# Monlock5x7_B.net
KiCad netlist of a schematic drawn in EAGLE
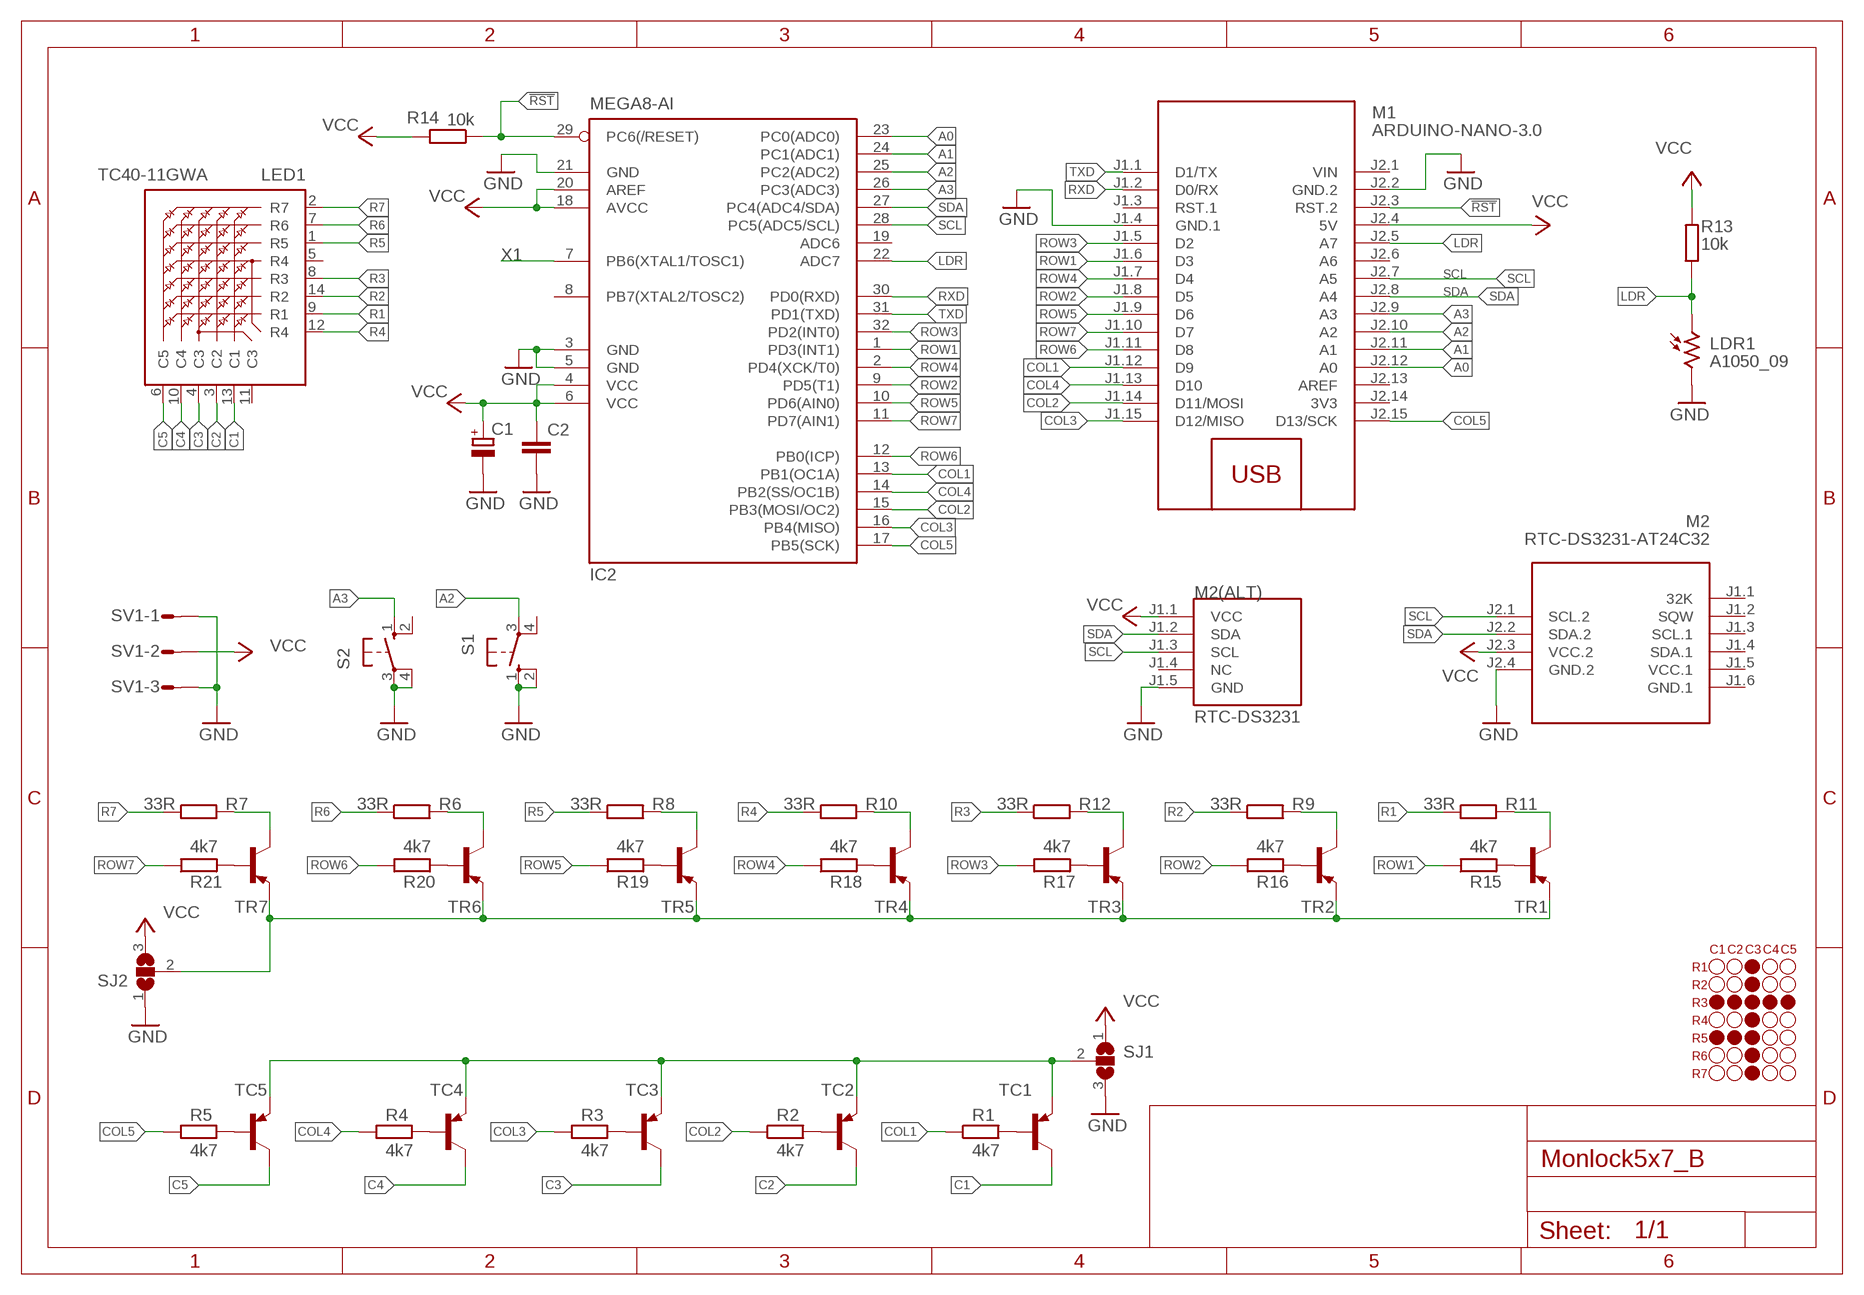
[diagram p0: schematic, sheet 1]

(export (version "E")
  (design (tool "Eeschema 10.0.6"))
  (components
    (comp (ref "C1")
      (value "CPOL-EU153CLV-0605")
      (footprint "eagle-import:153CLV-0605")
      (libsource (lib "eagle-import") (part "CPOL-EU153CLV-0605"))
    )
    (comp (ref "C2")
      (value "C-EUC0805K")
      (footprint "eagle-import:C0805K")
      (libsource (lib "eagle-import") (part "C-EUC0805K"))
    )
    (comp (ref "IC2")
      (value "MEGA8-AI")
      (footprint "eagle-import:TQFP32-08")
      (fields (field (name "MPN") "ATMEGA8-16AU"))
      (libsource (lib "eagle-import") (part "MEGA8-AI"))
    )
    (comp (ref "LDR1")
      (value "A1050_09")
      (footprint "eagle-import:T0-46-A10XX")
      (libsource (lib "eagle-import") (part "A1050_09"))
    )
    (comp (ref "LED1")
      (value "TC40-11GWA")
      (footprint "eagle-import:TC40-11GWA")
      (libsource (lib "eagle-import") (part "TC40-11GWA"))
    )
    (comp (ref "M1")
      (value "ARDUINO-NANO-3.0")
      (footprint "eagle-import:ARDUINO-NANO-3.0")
      (libsource (lib "eagle-import") (part "ARDUINO-NANO-3.0"))
    )
    (comp (ref "M2")
      (value "RTC-DS3231-AT24C32")
      (footprint "eagle-import:RTC-DS3231-AT24C32")
      (libsource (lib "eagle-import") (part "RTC-DS3231-AT24C32"))
    )
    (comp (ref "M2(ALT)")
      (value "RTC-DS3231")
      (footprint "eagle-import:RTC-DS3231_SMALL")
      (libsource (lib "eagle-import") (part "RTC-DS3231"))
    )
    (comp (ref "R1")
      (value "4k7")
      (footprint "eagle-import:0204_7")
      (libsource (lib "eagle-import") (part "R-EU_0204/7"))
    )
    (comp (ref "R2")
      (value "4k7")
      (footprint "eagle-import:0204_7")
      (libsource (lib "eagle-import") (part "R-EU_0204/7"))
    )
    (comp (ref "R3")
      (value "4k7")
      (footprint "eagle-import:0204_7")
      (libsource (lib "eagle-import") (part "R-EU_0204/7"))
    )
    (comp (ref "R4")
      (value "4k7")
      (footprint "eagle-import:0204_7")
      (libsource (lib "eagle-import") (part "R-EU_0204/7"))
    )
    (comp (ref "R5")
      (value "4k7")
      (footprint "eagle-import:0204_7")
      (libsource (lib "eagle-import") (part "R-EU_0204/7"))
    )
    (comp (ref "R6")
      (value "33R")
      (footprint "eagle-import:0204_7")
      (libsource (lib "eagle-import") (part "R-EU_0204/7"))
    )
    (comp (ref "R7")
      (value "33R")
      (footprint "eagle-import:0204_7")
      (libsource (lib "eagle-import") (part "R-EU_0204/7"))
    )
    (comp (ref "R8")
      (value "33R")
      (footprint "eagle-import:0204_7")
      (libsource (lib "eagle-import") (part "R-EU_0204/7"))
    )
    (comp (ref "R9")
      (value "33R")
      (footprint "eagle-import:0204_7")
      (libsource (lib "eagle-import") (part "R-EU_0204/7"))
    )
    (comp (ref "R10")
      (value "33R")
      (footprint "eagle-import:0204_7")
      (libsource (lib "eagle-import") (part "R-EU_0204/7"))
    )
    (comp (ref "R11")
      (value "33R")
      (footprint "eagle-import:0204_7")
      (libsource (lib "eagle-import") (part "R-EU_0204/7"))
    )
    (comp (ref "R12")
      (value "33R")
      (footprint "eagle-import:0204_7")
      (libsource (lib "eagle-import") (part "R-EU_0204/7"))
    )
    (comp (ref "R13")
      (value "10k")
      (footprint "eagle-import:0204_7")
      (libsource (lib "eagle-import") (part "R-EU_0204/7"))
    )
    (comp (ref "R14")
      (value "10k")
      (footprint "eagle-import:M0805")
      (libsource (lib "eagle-import") (part "R-EU_M0805"))
    )
    (comp (ref "R15")
      (value "4k7")
      (footprint "eagle-import:0204_7")
      (libsource (lib "eagle-import") (part "R-EU_0204/7"))
    )
    (comp (ref "R16")
      (value "4k7")
      (footprint "eagle-import:0204_7")
      (libsource (lib "eagle-import") (part "R-EU_0204/7"))
    )
    (comp (ref "R17")
      (value "4k7")
      (footprint "eagle-import:0204_7")
      (libsource (lib "eagle-import") (part "R-EU_0204/7"))
    )
    (comp (ref "R18")
      (value "4k7")
      (footprint "eagle-import:0204_7")
      (libsource (lib "eagle-import") (part "R-EU_0204/7"))
    )
    (comp (ref "R19")
      (value "4k7")
      (footprint "eagle-import:0204_7")
      (libsource (lib "eagle-import") (part "R-EU_0204/7"))
    )
    (comp (ref "R20")
      (value "4k7")
      (footprint "eagle-import:0204_7")
      (libsource (lib "eagle-import") (part "R-EU_0204/7"))
    )
    (comp (ref "R21")
      (value "4k7")
      (footprint "eagle-import:0204_7")
      (libsource (lib "eagle-import") (part "R-EU_0204/7"))
    )
    (comp (ref "S1")
      (value "40-XX")
      (footprint "eagle-import:B3F-40XX")
      (fields (field (name "MF") "OMRON COMPONENTS USA") (field (name "MPN") "B3F-4000"))
      (libsource (lib "eagle-import") (part "40-XX"))
    )
    (comp (ref "S2")
      (value "40-XX")
      (footprint "eagle-import:B3F-40XX")
      (fields (field (name "MF") "OMRON COMPONENTS USA") (field (name "MPN") "B3F-4000"))
      (libsource (lib "eagle-import") (part "40-XX"))
    )
    (comp (ref "SJ1")
      (value "SJ2W")
      (footprint "eagle-import:SJ_2")
      (libsource (lib "eagle-import") (part "SJ2W"))
    )
    (comp (ref "SJ2")
      (value "SJ2W")
      (footprint "eagle-import:SJ_2")
      (libsource (lib "eagle-import") (part "SJ2W"))
    )
    (comp (ref "SV1")
      (value "S03P")
      (footprint "eagle-import:S03P")
      (libsource (lib "eagle-import") (part "S03P"))
    )
    (comp (ref "TC1")
      (value "BC327-PNP-TO92-EBC")
      (footprint "eagle-import:TO92-EBC")
      (libsource (lib "eagle-import") (part "-PNP-TO92-EBCBC327"))
    )
    (comp (ref "TC2")
      (value "BC327-PNP-TO92-EBC")
      (footprint "eagle-import:TO92-EBC")
      (libsource (lib "eagle-import") (part "-PNP-TO92-EBCBC327"))
    )
    (comp (ref "TC3")
      (value "BC327-PNP-TO92-EBC")
      (footprint "eagle-import:TO92-EBC")
      (libsource (lib "eagle-import") (part "-PNP-TO92-EBCBC327"))
    )
    (comp (ref "TC4")
      (value "BC327-PNP-TO92-EBC")
      (footprint "eagle-import:TO92-EBC")
      (libsource (lib "eagle-import") (part "-PNP-TO92-EBCBC327"))
    )
    (comp (ref "TC5")
      (value "BC327-PNP-TO92-EBC")
      (footprint "eagle-import:TO92-EBC")
      (libsource (lib "eagle-import") (part "-PNP-TO92-EBCBC327"))
    )
    (comp (ref "TR1")
      (value "BC327-PNP-TO92-EBC")
      (footprint "eagle-import:TO92-EBC")
      (libsource (lib "eagle-import") (part "-PNP-TO92-EBCBC327"))
    )
    (comp (ref "TR2")
      (value "BC327-PNP-TO92-EBC")
      (footprint "eagle-import:TO92-EBC")
      (libsource (lib "eagle-import") (part "-PNP-TO92-EBCBC327"))
    )
    (comp (ref "TR3")
      (value "BC327-PNP-TO92-EBC")
      (footprint "eagle-import:TO92-EBC")
      (libsource (lib "eagle-import") (part "-PNP-TO92-EBCBC327"))
    )
    (comp (ref "TR4")
      (value "BC327-PNP-TO92-EBC")
      (footprint "eagle-import:TO92-EBC")
      (libsource (lib "eagle-import") (part "-PNP-TO92-EBCBC327"))
    )
    (comp (ref "TR5")
      (value "BC327-PNP-TO92-EBC")
      (footprint "eagle-import:TO92-EBC")
      (libsource (lib "eagle-import") (part "-PNP-TO92-EBCBC327"))
    )
    (comp (ref "TR6")
      (value "BC327-PNP-TO92-EBC")
      (footprint "eagle-import:TO92-EBC")
      (libsource (lib "eagle-import") (part "-PNP-TO92-EBCBC327"))
    )
    (comp (ref "TR7")
      (value "BC327-PNP-TO92-EBC")
      (footprint "eagle-import:TO92-EBC")
      (libsource (lib "eagle-import") (part "-PNP-TO92-EBCBC327"))
    )
  )
  (nets
    (net (code "1") (name "/3V3") (class "Default")
      (node (ref "M1") (pin "J2.14") (pinfunction "3V3_J2.14") (pintype "power_in"))
    )
    (net (code "2") (name "/GND.1") (class "Default")
      (node (ref "M2") (pin "J1.6") (pinfunction "GND.1_J1.6") (pintype "power_in"))
    )
    (net (code "3") (name "/VCC.1") (class "Default")
      (node (ref "M2") (pin "J1.5") (pinfunction "VCC.1_J1.5") (pintype "power_in"))
    )
    (net (code "4") (name "/VIN") (class "Default")
      (node (ref "M1") (pin "J2.1") (pinfunction "VIN_J2.1") (pintype "power_in"))
    )
    (net (code "5") (name "/X1") (class "Default")
      (node (ref "IC2") (pin "7") (pinfunction "PB6(XTAL1/TOSC1)_7") (pintype "bidirectional"))
    )
    (net (code "6") (name "/~{RST}") (class "Default")
      (node (ref "IC2") (pin "29") (pinfunction "PC6(/RESET)_29") (pintype "bidirectional"))
      (node (ref "M1") (pin "J2.3") (pinfunction "RST.2_J2.3") (pintype "bidirectional"))
      (node (ref "R14") (pin "1") (pinfunction "1_1") (pintype "passive"))
    )
    (net (code "7") (name "A0") (class "Default")
      (node (ref "IC2") (pin "23") (pinfunction "PC0(ADC0)_23") (pintype "bidirectional"))
      (node (ref "M1") (pin "J2.12") (pinfunction "A0_J2.12") (pintype "bidirectional"))
    )
    (net (code "8") (name "A1") (class "Default")
      (node (ref "IC2") (pin "24") (pinfunction "PC1(ADC1)_24") (pintype "bidirectional"))
      (node (ref "M1") (pin "J2.11") (pinfunction "A1_J2.11") (pintype "bidirectional"))
    )
    (net (code "9") (name "A2") (class "Default")
      (node (ref "IC2") (pin "25") (pinfunction "PC2(ADC2)_25") (pintype "bidirectional"))
      (node (ref "M1") (pin "J2.10") (pinfunction "A2_J2.10") (pintype "bidirectional"))
      (node (ref "S1") (pin "3") (pinfunction "P_3") (pintype "passive"))
    )
    (net (code "10") (name "A3") (class "Default")
      (node (ref "IC2") (pin "26") (pinfunction "PC3(ADC3)_26") (pintype "bidirectional"))
      (node (ref "M1") (pin "J2.9") (pinfunction "A3_J2.9") (pintype "bidirectional"))
      (node (ref "S2") (pin "1") (pinfunction "S_1") (pintype "passive"))
    )
    (net (code "11") (name "C1") (class "Default")
      (node (ref "LED1") (pin "13") (pinfunction "C1_13") (pintype "passive"))
      (node (ref "TC1") (pin "C") (pinfunction "C_C") (pintype "passive"))
    )
    (net (code "12") (name "C2") (class "Default")
      (node (ref "LED1") (pin "3") (pinfunction "C2_3") (pintype "passive"))
      (node (ref "TC2") (pin "C") (pinfunction "C_C") (pintype "passive"))
    )
    (net (code "13") (name "C3") (class "Default")
      (node (ref "LED1") (pin "4") (pinfunction "C3_4") (pintype "passive"))
      (node (ref "TC3") (pin "C") (pinfunction "C_C") (pintype "passive"))
    )
    (net (code "14") (name "C4") (class "Default")
      (node (ref "LED1") (pin "10") (pinfunction "C4_10") (pintype "passive"))
      (node (ref "TC4") (pin "C") (pinfunction "C_C") (pintype "passive"))
    )
    (net (code "15") (name "C5") (class "Default")
      (node (ref "LED1") (pin "6") (pinfunction "C5_6") (pintype "passive"))
      (node (ref "TC5") (pin "C") (pinfunction "C_C") (pintype "passive"))
    )
    (net (code "16") (name "COL1") (class "Default")
      (node (ref "IC2") (pin "13") (pinfunction "PB1(OC1A)_13") (pintype "bidirectional"))
      (node (ref "M1") (pin "J1.12") (pinfunction "D9_J1.12") (pintype "bidirectional"))
      (node (ref "R1") (pin "1") (pinfunction "1_1") (pintype "passive"))
    )
    (net (code "17") (name "COL2") (class "Default")
      (node (ref "IC2") (pin "15") (pinfunction "PB3(MOSI/OC2)_15") (pintype "bidirectional"))
      (node (ref "M1") (pin "J1.14") (pinfunction "D11/MOSI_J1.14") (pintype "bidirectional"))
      (node (ref "R2") (pin "1") (pinfunction "1_1") (pintype "passive"))
    )
    (net (code "18") (name "COL3") (class "Default")
      (node (ref "IC2") (pin "16") (pinfunction "PB4(MISO)_16") (pintype "bidirectional"))
      (node (ref "M1") (pin "J1.15") (pinfunction "D12/MISO_J1.15") (pintype "bidirectional"))
      (node (ref "R3") (pin "1") (pinfunction "1_1") (pintype "passive"))
    )
    (net (code "19") (name "COL4") (class "Default")
      (node (ref "IC2") (pin "14") (pinfunction "PB2(SS/OC1B)_14") (pintype "bidirectional"))
      (node (ref "M1") (pin "J1.13") (pinfunction "D10_J1.13") (pintype "bidirectional"))
      (node (ref "R4") (pin "1") (pinfunction "1_1") (pintype "passive"))
    )
    (net (code "20") (name "COL5") (class "Default")
      (node (ref "IC2") (pin "17") (pinfunction "PB5(SCK)_17") (pintype "bidirectional"))
      (node (ref "M1") (pin "J2.15") (pinfunction "D13/SCK_J2.15") (pintype "bidirectional"))
      (node (ref "R5") (pin "1") (pinfunction "1_1") (pintype "passive"))
    )
    (net (code "21") (name "GND") (class "Default")
      (node (ref "C1") (pin "-") (pinfunction "-_-") (pintype "passive"))
      (node (ref "C2") (pin "2") (pinfunction "2_2") (pintype "passive"))
      (node (ref "IC2") (pin "21") (pinfunction "GND_21") (pintype "power_in"))
      (node (ref "IC2") (pin "3") (pinfunction "GND_3") (pintype "power_in"))
      (node (ref "IC2") (pin "5") (pinfunction "GND_5") (pintype "power_in"))
      (node (ref "LDR1") (pin "2") (pinfunction "2_2") (pintype "passive"))
      (node (ref "M1") (pin "J1.4") (pinfunction "GND.1_J1.4") (pintype "power_in"))
      (node (ref "M1") (pin "J2.2") (pinfunction "GND.2_J2.2") (pintype "power_in"))
      (node (ref "M2") (pin "J2.4") (pinfunction "GND.2_J2.4") (pintype "power_in"))
      (node (ref "M2(ALT)") (pin "J1.5") (pinfunction "GND_J1.5") (pintype "power_in"))
      (node (ref "S1") (pin "1") (pinfunction "S_1") (pintype "passive"))
      (node (ref "S1") (pin "2") (pinfunction "S1_2") (pintype "passive"))
      (node (ref "S2") (pin "3") (pinfunction "P_3") (pintype "passive"))
      (node (ref "S2") (pin "4") (pinfunction "P1_4") (pintype "passive"))
      (node (ref "SJ1") (pin "3") (pinfunction "3_3") (pintype "passive"))
      (node (ref "SJ2") (pin "1") (pinfunction "1_1") (pintype "passive"))
      (node (ref "SV1") (pin "1") (pinfunction "S_1") (pintype "passive"))
      (node (ref "SV1") (pin "3") (pinfunction "S_3") (pintype "passive"))
    )
    (net (code "22") (name "LDR") (class "Default")
      (node (ref "IC2") (pin "22") (pinfunction "ADC7_22") (pintype "bidirectional"))
      (node (ref "LDR1") (pin "1") (pinfunction "1_1") (pintype "passive"))
      (node (ref "M1") (pin "J2.5") (pinfunction "A7_J2.5") (pintype "bidirectional"))
      (node (ref "R13") (pin "1") (pinfunction "1_1") (pintype "passive"))
    )
    (net (code "23") (name "Net-(R1-Pad2)") (class "Default")
      (node (ref "R1") (pin "2") (pinfunction "2_2") (pintype "passive"))
      (node (ref "TC1") (pin "B") (pinfunction "B_B") (pintype "passive"))
    )
    (net (code "24") (name "Net-(R2-Pad2)") (class "Default")
      (node (ref "R2") (pin "2") (pinfunction "2_2") (pintype "passive"))
      (node (ref "TC2") (pin "B") (pinfunction "B_B") (pintype "passive"))
    )
    (net (code "25") (name "Net-(R3-Pad2)") (class "Default")
      (node (ref "R3") (pin "2") (pinfunction "2_2") (pintype "passive"))
      (node (ref "TC3") (pin "B") (pinfunction "B_B") (pintype "passive"))
    )
    (net (code "26") (name "Net-(R4-Pad2)") (class "Default")
      (node (ref "R4") (pin "2") (pinfunction "2_2") (pintype "passive"))
      (node (ref "TC4") (pin "B") (pinfunction "B_B") (pintype "passive"))
    )
    (net (code "27") (name "Net-(R5-Pad2)") (class "Default")
      (node (ref "R5") (pin "2") (pinfunction "2_2") (pintype "passive"))
      (node (ref "TC5") (pin "B") (pinfunction "B_B") (pintype "passive"))
    )
    (net (code "28") (name "Net-(R6-Pad2)") (class "Default")
      (node (ref "R6") (pin "2") (pinfunction "2_2") (pintype "passive"))
      (node (ref "TR6") (pin "C") (pinfunction "C_C") (pintype "passive"))
    )
    (net (code "29") (name "Net-(R7-Pad2)") (class "Default")
      (node (ref "R7") (pin "2") (pinfunction "2_2") (pintype "passive"))
      (node (ref "TR7") (pin "C") (pinfunction "C_C") (pintype "passive"))
    )
    (net (code "30") (name "Net-(R8-Pad2)") (class "Default")
      (node (ref "R8") (pin "2") (pinfunction "2_2") (pintype "passive"))
      (node (ref "TR5") (pin "C") (pinfunction "C_C") (pintype "passive"))
    )
    (net (code "31") (name "Net-(R9-Pad2)") (class "Default")
      (node (ref "R9") (pin "2") (pinfunction "2_2") (pintype "passive"))
      (node (ref "TR2") (pin "C") (pinfunction "C_C") (pintype "passive"))
    )
    (net (code "32") (name "Net-(R10-Pad2)") (class "Default")
      (node (ref "R10") (pin "2") (pinfunction "2_2") (pintype "passive"))
      (node (ref "TR4") (pin "C") (pinfunction "C_C") (pintype "passive"))
    )
    (net (code "33") (name "Net-(R11-Pad2)") (class "Default")
      (node (ref "R11") (pin "2") (pinfunction "2_2") (pintype "passive"))
      (node (ref "TR1") (pin "C") (pinfunction "C_C") (pintype "passive"))
    )
    (net (code "34") (name "Net-(R12-Pad2)") (class "Default")
      (node (ref "R12") (pin "2") (pinfunction "2_2") (pintype "passive"))
      (node (ref "TR3") (pin "C") (pinfunction "C_C") (pintype "passive"))
    )
    (net (code "35") (name "Net-(R15-Pad2)") (class "Default")
      (node (ref "R15") (pin "2") (pinfunction "2_2") (pintype "passive"))
      (node (ref "TR1") (pin "B") (pinfunction "B_B") (pintype "passive"))
    )
    (net (code "36") (name "Net-(R16-Pad2)") (class "Default")
      (node (ref "R16") (pin "2") (pinfunction "2_2") (pintype "passive"))
      (node (ref "TR2") (pin "B") (pinfunction "B_B") (pintype "passive"))
    )
    (net (code "37") (name "Net-(R17-Pad2)") (class "Default")
      (node (ref "R17") (pin "2") (pinfunction "2_2") (pintype "passive"))
      (node (ref "TR3") (pin "B") (pinfunction "B_B") (pintype "passive"))
    )
    (net (code "38") (name "Net-(R18-Pad2)") (class "Default")
      (node (ref "R18") (pin "2") (pinfunction "2_2") (pintype "passive"))
      (node (ref "TR4") (pin "B") (pinfunction "B_B") (pintype "passive"))
    )
    (net (code "39") (name "Net-(R19-Pad2)") (class "Default")
      (node (ref "R19") (pin "2") (pinfunction "2_2") (pintype "passive"))
      (node (ref "TR5") (pin "B") (pinfunction "B_B") (pintype "passive"))
    )
    (net (code "40") (name "Net-(R20-Pad2)") (class "Default")
      (node (ref "R20") (pin "2") (pinfunction "2_2") (pintype "passive"))
      (node (ref "TR6") (pin "B") (pinfunction "B_B") (pintype "passive"))
    )
    (net (code "41") (name "Net-(R21-Pad2)") (class "Default")
      (node (ref "R21") (pin "2") (pinfunction "2_2") (pintype "passive"))
      (node (ref "TR7") (pin "B") (pinfunction "B_B") (pintype "passive"))
    )
    (net (code "42") (name "Net-(SJ1-Pad2)") (class "Default")
      (node (ref "SJ1") (pin "2") (pinfunction "2_2") (pintype "passive"))
      (node (ref "TC1") (pin "E") (pinfunction "E_E") (pintype "passive"))
      (node (ref "TC2") (pin "E") (pinfunction "E_E") (pintype "passive"))
      (node (ref "TC3") (pin "E") (pinfunction "E_E") (pintype "passive"))
      (node (ref "TC4") (pin "E") (pinfunction "E_E") (pintype "passive"))
      (node (ref "TC5") (pin "E") (pinfunction "E_E") (pintype "passive"))
    )
    (net (code "43") (name "Net-(SJ2-Pad2)") (class "Default")
      (node (ref "SJ2") (pin "2") (pinfunction "2_2") (pintype "passive"))
      (node (ref "TR1") (pin "E") (pinfunction "E_E") (pintype "passive"))
      (node (ref "TR2") (pin "E") (pinfunction "E_E") (pintype "passive"))
      (node (ref "TR3") (pin "E") (pinfunction "E_E") (pintype "passive"))
      (node (ref "TR4") (pin "E") (pinfunction "E_E") (pintype "passive"))
      (node (ref "TR5") (pin "E") (pinfunction "E_E") (pintype "passive"))
      (node (ref "TR6") (pin "E") (pinfunction "E_E") (pintype "passive"))
      (node (ref "TR7") (pin "E") (pinfunction "E_E") (pintype "passive"))
    )
    (net (code "44") (name "R1") (class "Default")
      (node (ref "LED1") (pin "9") (pinfunction "R1_9") (pintype "passive"))
      (node (ref "R11") (pin "1") (pinfunction "1_1") (pintype "passive"))
    )
    (net (code "45") (name "R2") (class "Default")
      (node (ref "LED1") (pin "14") (pinfunction "R2_14") (pintype "passive"))
      (node (ref "R9") (pin "1") (pinfunction "1_1") (pintype "passive"))
    )
    (net (code "46") (name "R3") (class "Default")
      (node (ref "LED1") (pin "8") (pinfunction "R3_8") (pintype "passive"))
      (node (ref "R12") (pin "1") (pinfunction "1_1") (pintype "passive"))
    )
    (net (code "47") (name "R4") (class "Default")
      (node (ref "LED1") (pin "12") (pinfunction "R4_12") (pintype "passive"))
      (node (ref "R10") (pin "1") (pinfunction "1_1") (pintype "passive"))
    )
    (net (code "48") (name "R5") (class "Default")
      (node (ref "LED1") (pin "1") (pinfunction "R5_1") (pintype "passive"))
      (node (ref "R8") (pin "1") (pinfunction "1_1") (pintype "passive"))
    )
    (net (code "49") (name "R6") (class "Default")
      (node (ref "LED1") (pin "7") (pinfunction "R6_7") (pintype "passive"))
      (node (ref "R6") (pin "1") (pinfunction "1_1") (pintype "passive"))
    )
    (net (code "50") (name "R7") (class "Default")
      (node (ref "LED1") (pin "2") (pinfunction "R7_2") (pintype "passive"))
      (node (ref "R7") (pin "1") (pinfunction "1_1") (pintype "passive"))
    )
    (net (code "51") (name "ROW1") (class "Default")
      (node (ref "IC2") (pin "1") (pinfunction "PD3(INT1)_1") (pintype "bidirectional"))
      (node (ref "M1") (pin "J1.6") (pinfunction "D3_J1.6") (pintype "bidirectional"))
      (node (ref "R15") (pin "1") (pinfunction "1_1") (pintype "passive"))
    )
    (net (code "52") (name "ROW2") (class "Default")
      (node (ref "IC2") (pin "9") (pinfunction "PD5(T1)_9") (pintype "bidirectional"))
      (node (ref "M1") (pin "J1.8") (pinfunction "D5_J1.8") (pintype "bidirectional"))
      (node (ref "R16") (pin "1") (pinfunction "1_1") (pintype "passive"))
    )
    (net (code "53") (name "ROW3") (class "Default")
      (node (ref "IC2") (pin "32") (pinfunction "PD2(INT0)_32") (pintype "bidirectional"))
      (node (ref "M1") (pin "J1.5") (pinfunction "D2_J1.5") (pintype "bidirectional"))
      (node (ref "R17") (pin "1") (pinfunction "1_1") (pintype "passive"))
    )
    (net (code "54") (name "ROW4") (class "Default")
      (node (ref "IC2") (pin "2") (pinfunction "PD4(XCK/T0)_2") (pintype "bidirectional"))
      (node (ref "M1") (pin "J1.7") (pinfunction "D4_J1.7") (pintype "bidirectional"))
      (node (ref "R18") (pin "1") (pinfunction "1_1") (pintype "passive"))
    )
    (net (code "55") (name "ROW5") (class "Default")
      (node (ref "IC2") (pin "10") (pinfunction "PD6(AIN0)_10") (pintype "bidirectional"))
      (node (ref "M1") (pin "J1.9") (pinfunction "D6_J1.9") (pintype "bidirectional"))
      (node (ref "R19") (pin "1") (pinfunction "1_1") (pintype "passive"))
    )
    (net (code "56") (name "ROW6") (class "Default")
      (node (ref "IC2") (pin "12") (pinfunction "PB0(ICP)_12") (pintype "bidirectional"))
      (node (ref "M1") (pin "J1.11") (pinfunction "D8_J1.11") (pintype "bidirectional"))
      (node (ref "R20") (pin "1") (pinfunction "1_1") (pintype "passive"))
    )
    (net (code "57") (name "ROW7") (class "Default")
      (node (ref "IC2") (pin "11") (pinfunction "PD7(AIN1)_11") (pintype "bidirectional"))
      (node (ref "M1") (pin "J1.10") (pinfunction "D7_J1.10") (pintype "bidirectional"))
      (node (ref "R21") (pin "1") (pinfunction "1_1") (pintype "passive"))
    )
    (net (code "58") (name "RXD") (class "Default")
      (node (ref "IC2") (pin "30") (pinfunction "PD0(RXD)_30") (pintype "bidirectional"))
      (node (ref "M1") (pin "J1.2") (pinfunction "D0/RX_J1.2") (pintype "bidirectional"))
    )
    (net (code "59") (name "SCL") (class "Default")
      (node (ref "IC2") (pin "28") (pinfunction "PC5(ADC5/SCL)_28") (pintype "bidirectional"))
      (node (ref "M1") (pin "J2.7") (pinfunction "A5_J2.7") (pintype "bidirectional"))
      (node (ref "M2") (pin "J2.1") (pinfunction "SCL.2_J2.1") (pintype "bidirectional"))
      (node (ref "M2(ALT)") (pin "J1.3") (pinfunction "SCL_J1.3") (pintype "bidirectional"))
    )
    (net (code "60") (name "SDA") (class "Default")
      (node (ref "IC2") (pin "27") (pinfunction "PC4(ADC4/SDA)_27") (pintype "bidirectional"))
      (node (ref "M1") (pin "J2.8") (pinfunction "A4_J2.8") (pintype "bidirectional"))
      (node (ref "M2") (pin "J2.2") (pinfunction "SDA.2_J2.2") (pintype "bidirectional"))
      (node (ref "M2(ALT)") (pin "J1.2") (pinfunction "SDA_J1.2") (pintype "bidirectional"))
    )
    (net (code "61") (name "TXD") (class "Default")
      (node (ref "IC2") (pin "31") (pinfunction "PD1(TXD)_31") (pintype "bidirectional"))
      (node (ref "M1") (pin "J1.1") (pinfunction "D1/TX_J1.1") (pintype "bidirectional"))
    )
    (net (code "62") (name "VCC") (class "Default")
      (node (ref "C1") (pin "+") (pinfunction "+_+") (pintype "passive"))
      (node (ref "C2") (pin "1") (pinfunction "1_1") (pintype "passive"))
      (node (ref "IC2") (pin "18") (pinfunction "AVCC_18") (pintype "power_in"))
      (node (ref "IC2") (pin "20") (pinfunction "AREF_20") (pintype "passive"))
      (node (ref "IC2") (pin "4") (pinfunction "VCC_4") (pintype "power_in"))
      (node (ref "IC2") (pin "6") (pinfunction "VCC_6") (pintype "power_in"))
      (node (ref "M1") (pin "J2.4") (pinfunction "5V_J2.4") (pintype "power_in"))
      (node (ref "M2") (pin "J2.3") (pinfunction "VCC.2_J2.3") (pintype "power_in"))
      (node (ref "M2(ALT)") (pin "J1.1") (pinfunction "VCC_J1.1") (pintype "power_in"))
      (node (ref "R13") (pin "2") (pinfunction "2_2") (pintype "passive"))
      (node (ref "R14") (pin "2") (pinfunction "2_2") (pintype "passive"))
      (node (ref "SJ1") (pin "1") (pinfunction "1_1") (pintype "passive"))
      (node (ref "SJ2") (pin "3") (pinfunction "3_3") (pintype "passive"))
      (node (ref "SV1") (pin "2") (pinfunction "S_2") (pintype "passive"))
    )
    (net (code "63") (name "unconnected-(IC2-ADC6-Pad19)") (class "Default")
      (node (ref "IC2") (pin "19") (pinfunction "ADC6_19") (pintype "bidirectional"))
    )
    (net (code "64") (name "unconnected-(IC2-PB7(XTAL2{slash}TOSC2)-Pad8)") (class "Default")
      (node (ref "IC2") (pin "8") (pinfunction "PB7(XTAL2/TOSC2)_8") (pintype "bidirectional"))
    )
    (net (code "65") (name "unconnected-(LED1-C3-Pad11)") (class "Default")
      (node (ref "LED1") (pin "11") (pinfunction "C3_11") (pintype "passive"))
    )
    (net (code "66") (name "unconnected-(LED1-R4-Pad5)") (class "Default")
      (node (ref "LED1") (pin "5") (pinfunction "R4_5") (pintype "passive"))
    )
    (net (code "67") (name "unconnected-(M1-A6-PadJ2.6)") (class "Default")
      (node (ref "M1") (pin "J2.6") (pinfunction "A6_J2.6") (pintype "bidirectional"))
    )
    (net (code "68") (name "unconnected-(M1-AREF-PadJ2.13)") (class "Default")
      (node (ref "M1") (pin "J2.13") (pinfunction "AREF_J2.13") (pintype "bidirectional"))
    )
    (net (code "69") (name "unconnected-(M1-RST.1-PadJ1.3)") (class "Default")
      (node (ref "M1") (pin "J1.3") (pinfunction "RST.1_J1.3") (pintype "bidirectional"))
    )
    (net (code "70") (name "unconnected-(M2(ALT)-NC-PadJ1.4)") (class "Default")
      (node (ref "M2(ALT)") (pin "J1.4") (pinfunction "NC_J1.4") (pintype "bidirectional"))
    )
    (net (code "71") (name "unconnected-(M2-32K-PadJ1.1)") (class "Default")
      (node (ref "M2") (pin "J1.1") (pinfunction "32K_J1.1") (pintype "bidirectional"))
    )
    (net (code "72") (name "unconnected-(M2-SCL.1-PadJ1.3)") (class "Default")
      (node (ref "M2") (pin "J1.3") (pinfunction "SCL.1_J1.3") (pintype "bidirectional"))
    )
    (net (code "73") (name "unconnected-(M2-SDA.1-PadJ1.4)") (class "Default")
      (node (ref "M2") (pin "J1.4") (pinfunction "SDA.1_J1.4") (pintype "bidirectional"))
    )
    (net (code "74") (name "unconnected-(M2-SQW-PadJ1.2)") (class "Default")
      (node (ref "M2") (pin "J1.2") (pinfunction "SQW_J1.2") (pintype "bidirectional"))
    )
    (net (code "75") (name "unconnected-(S1-P1-Pad4)") (class "Default")
      (node (ref "S1") (pin "4") (pinfunction "P1_4") (pintype "passive"))
    )
    (net (code "76") (name "unconnected-(S2-S1-Pad2)") (class "Default")
      (node (ref "S2") (pin "2") (pinfunction "S1_2") (pintype "passive"))
    )
  )
)
